# EKG_Modul_Versorgung.net
KiCad netlist of a schematic drawn in EAGLE
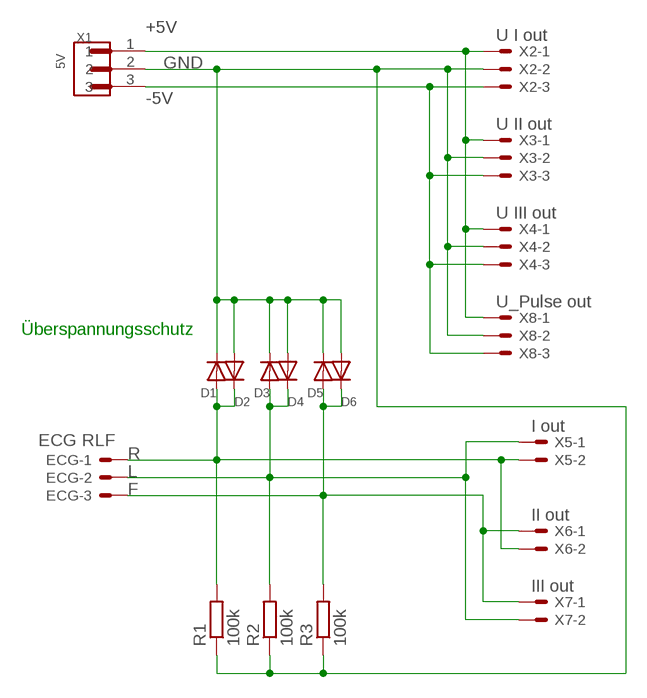
[diagram p0: schematic, sheet 1]

(export (version "E")
  (design (tool "Eeschema 10.0.6"))
  (components
    (comp (ref "D1")
      (value "DIODEDO-1N4148")
      (footprint "eagle-import:DO-1N4148")
      (libsource (lib "eagle-import") (part "DIODEDO-1N4148"))
    )
    (comp (ref "D2")
      (value "DIODEDO-1N4148")
      (footprint "eagle-import:DO-1N4148")
      (libsource (lib "eagle-import") (part "DIODEDO-1N4148"))
    )
    (comp (ref "D3")
      (value "DIODEDO-1N4148")
      (footprint "eagle-import:DO-1N4148")
      (libsource (lib "eagle-import") (part "DIODEDO-1N4148"))
    )
    (comp (ref "D4")
      (value "DIODEDO-1N4148")
      (footprint "eagle-import:DO-1N4148")
      (libsource (lib "eagle-import") (part "DIODEDO-1N4148"))
    )
    (comp (ref "D5")
      (value "DIODEDO-1N4148")
      (footprint "eagle-import:DO-1N4148")
      (libsource (lib "eagle-import") (part "DIODEDO-1N4148"))
    )
    (comp (ref "D6")
      (value "DIODEDO-1N4148")
      (footprint "eagle-import:DO-1N4148")
      (libsource (lib "eagle-import") (part "DIODEDO-1N4148"))
    )
    (comp (ref "ECG")
      (value "ECG RLF")
      (footprint "eagle-import:JST-XH-03-PACKAGE-LONG-PAD")
      (libsource (lib "eagle-import") (part "JST-XH-03-PIN-LONG-PAD"))
    )
    (comp (ref "R1")
      (value "100k")
      (footprint "eagle-import:0207_7")
      (libsource (lib "eagle-import") (part "R-EU_0207/7"))
    )
    (comp (ref "R2")
      (value "100k")
      (footprint "eagle-import:0207_7")
      (libsource (lib "eagle-import") (part "R-EU_0207/7"))
    )
    (comp (ref "R3")
      (value "100k")
      (footprint "eagle-import:0207_7")
      (libsource (lib "eagle-import") (part "R-EU_0207/7"))
    )
    (comp (ref "X1")
      (value "5V")
      (footprint "eagle-import:JST_B3P-VH(LF)(SN)")
      (fields (field (name "MF") "JST") (field (name "MP") "B3P-VH_LF__SN_"))
      (libsource (lib "eagle-import") (part "B3P-VH(LF)(SN)"))
    )
    (comp (ref "X2")
      (value "U I out")
      (footprint "eagle-import:JST-XH-03-PACKAGE-LONG-PAD")
      (libsource (lib "eagle-import") (part "JST-XH-03-PIN-LONG-PAD"))
    )
    (comp (ref "X3")
      (value "U II out")
      (footprint "eagle-import:JST-XH-03-PACKAGE-LONG-PAD")
      (libsource (lib "eagle-import") (part "JST-XH-03-PIN-LONG-PAD"))
    )
    (comp (ref "X4")
      (value "U III out")
      (footprint "eagle-import:JST-XH-03-PACKAGE-LONG-PAD")
      (libsource (lib "eagle-import") (part "JST-XH-03-PIN-LONG-PAD"))
    )
    (comp (ref "X5")
      (value "I out")
      (footprint "eagle-import:JST-XH-02-PACKAGE-LONG-PAD")
      (libsource (lib "eagle-import") (part "JST-XH-02-PIN-LONG-PAD"))
    )
    (comp (ref "X6")
      (value "II out")
      (footprint "eagle-import:JST-XH-02-PACKAGE-LONG-PAD")
      (libsource (lib "eagle-import") (part "JST-XH-02-PIN-LONG-PAD"))
    )
    (comp (ref "X7")
      (value "III out")
      (footprint "eagle-import:JST-XH-02-PACKAGE-LONG-PAD")
      (libsource (lib "eagle-import") (part "JST-XH-02-PIN-LONG-PAD"))
    )
    (comp (ref "X8")
      (value "U_Pulse out")
      (footprint "eagle-import:JST-XH-03-PACKAGE-LONG-PAD")
      (libsource (lib "eagle-import") (part "JST-XH-03-PIN-LONG-PAD"))
    )
  )
  (nets
    (net (code "1") (name "/+5V") (class "Default")
      (node (ref "X1") (pin "1") (pinfunction "1_1") (pintype "passive"))
      (node (ref "X2") (pin "1") (pinfunction "S_1") (pintype "passive"))
      (node (ref "X3") (pin "1") (pinfunction "S_1") (pintype "passive"))
      (node (ref "X4") (pin "1") (pinfunction "S_1") (pintype "passive"))
      (node (ref "X8") (pin "1") (pinfunction "S_1") (pintype "passive"))
    )
    (net (code "2") (name "/-5V") (class "Default")
      (node (ref "X1") (pin "3") (pinfunction "3_3") (pintype "passive"))
      (node (ref "X2") (pin "3") (pinfunction "S_3") (pintype "passive"))
      (node (ref "X3") (pin "3") (pinfunction "S_3") (pintype "passive"))
      (node (ref "X4") (pin "3") (pinfunction "S_3") (pintype "passive"))
      (node (ref "X8") (pin "3") (pinfunction "S_3") (pintype "passive"))
    )
    (net (code "3") (name "/F") (class "Default")
      (node (ref "D5") (pin "A") (pinfunction "A_A") (pintype "passive"))
      (node (ref "D6") (pin "C") (pinfunction "C_C") (pintype "passive"))
      (node (ref "ECG") (pin "3") (pinfunction "S_3") (pintype "passive"))
      (node (ref "R3") (pin "2") (pinfunction "2_2") (pintype "passive"))
      (node (ref "X6") (pin "1") (pinfunction "S_1") (pintype "passive"))
      (node (ref "X7") (pin "1") (pinfunction "S_1") (pintype "passive"))
    )
    (net (code "4") (name "/GND") (class "Default")
      (node (ref "D1") (pin "C") (pinfunction "C_C") (pintype "passive"))
      (node (ref "D2") (pin "A") (pinfunction "A_A") (pintype "passive"))
      (node (ref "D3") (pin "C") (pinfunction "C_C") (pintype "passive"))
      (node (ref "D4") (pin "A") (pinfunction "A_A") (pintype "passive"))
      (node (ref "D5") (pin "C") (pinfunction "C_C") (pintype "passive"))
      (node (ref "D6") (pin "A") (pinfunction "A_A") (pintype "passive"))
      (node (ref "R1") (pin "1") (pinfunction "1_1") (pintype "passive"))
      (node (ref "R2") (pin "1") (pinfunction "1_1") (pintype "passive"))
      (node (ref "R3") (pin "1") (pinfunction "1_1") (pintype "passive"))
      (node (ref "X1") (pin "2") (pinfunction "2_2") (pintype "passive"))
      (node (ref "X2") (pin "2") (pinfunction "S_2") (pintype "passive"))
      (node (ref "X3") (pin "2") (pinfunction "S_2") (pintype "passive"))
      (node (ref "X4") (pin "2") (pinfunction "S_2") (pintype "passive"))
      (node (ref "X8") (pin "2") (pinfunction "S_2") (pintype "passive"))
    )
    (net (code "5") (name "/L") (class "Default")
      (node (ref "D3") (pin "A") (pinfunction "A_A") (pintype "passive"))
      (node (ref "D4") (pin "C") (pinfunction "C_C") (pintype "passive"))
      (node (ref "ECG") (pin "2") (pinfunction "S_2") (pintype "passive"))
      (node (ref "R2") (pin "2") (pinfunction "2_2") (pintype "passive"))
      (node (ref "X5") (pin "1") (pinfunction "S_1") (pintype "passive"))
      (node (ref "X7") (pin "2") (pinfunction "S_2") (pintype "passive"))
    )
    (net (code "6") (name "/R") (class "Default")
      (node (ref "D1") (pin "A") (pinfunction "A_A") (pintype "passive"))
      (node (ref "D2") (pin "C") (pinfunction "C_C") (pintype "passive"))
      (node (ref "ECG") (pin "1") (pinfunction "S_1") (pintype "passive"))
      (node (ref "R1") (pin "2") (pinfunction "2_2") (pintype "passive"))
      (node (ref "X5") (pin "2") (pinfunction "S_2") (pintype "passive"))
      (node (ref "X6") (pin "2") (pinfunction "S_2") (pintype "passive"))
    )
  )
)
